# schematic.net
KiCad netlist of a schematic drawn in EasyEDA
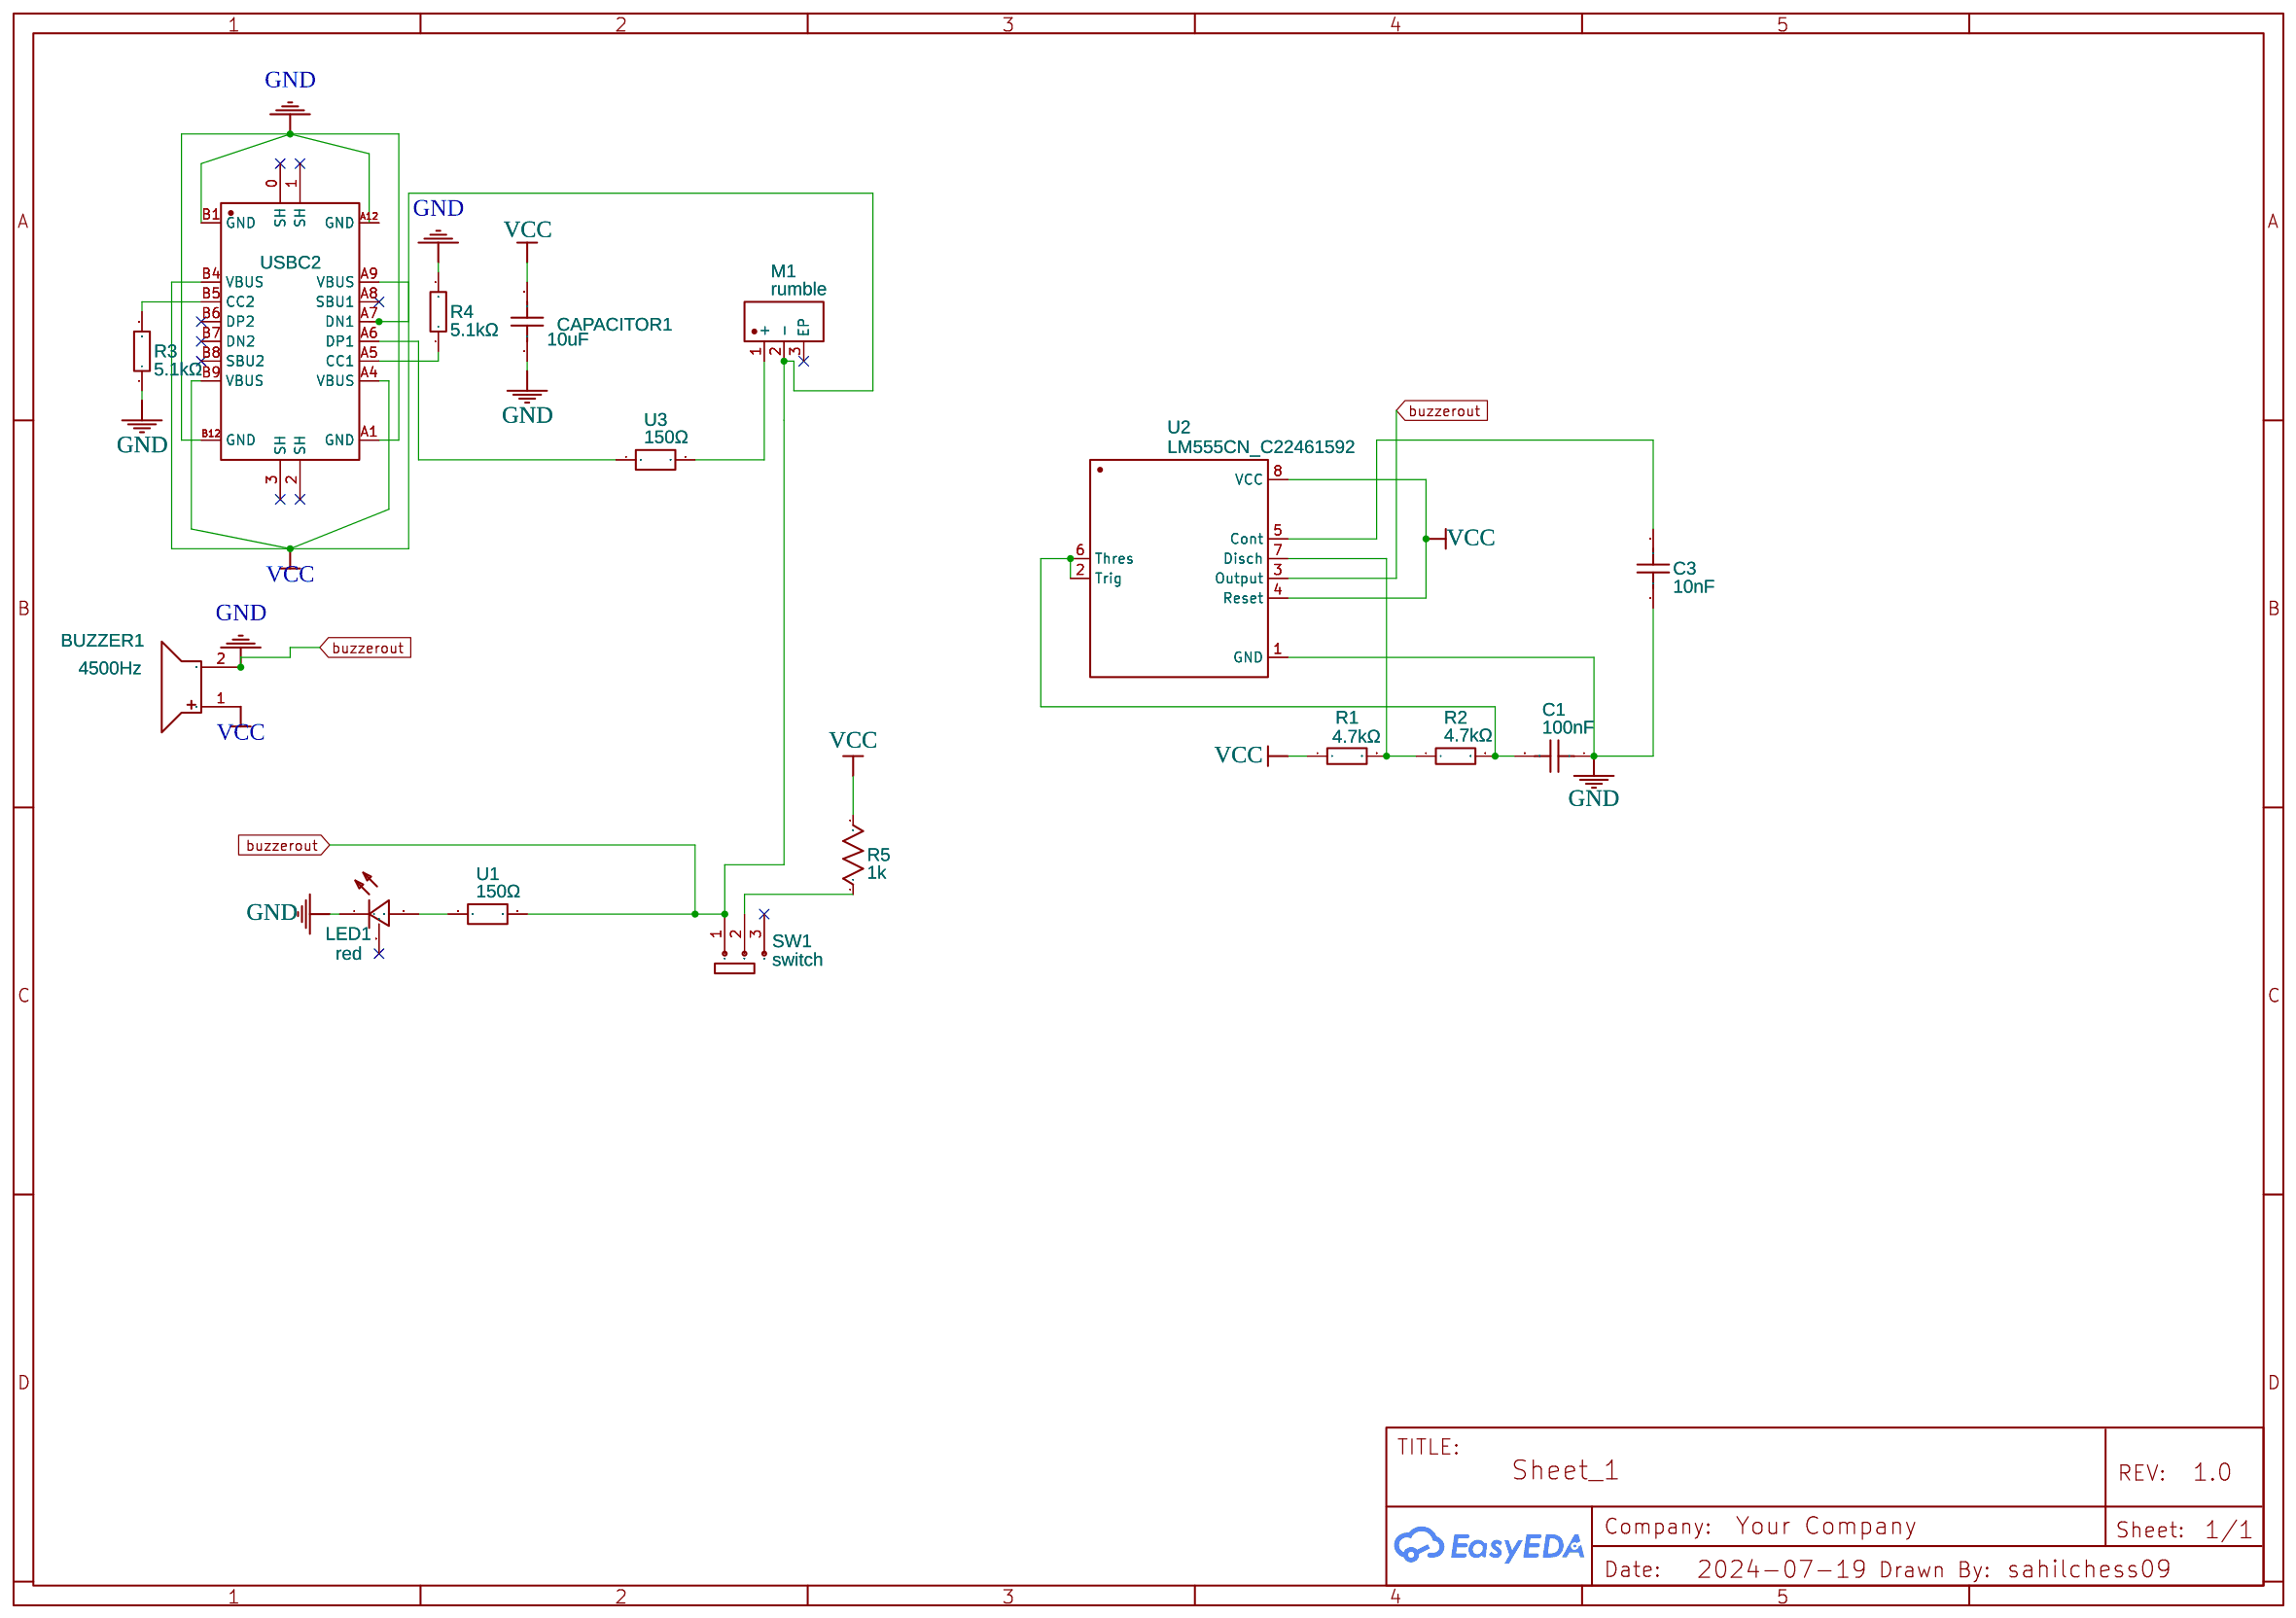
[diagram p0: schematic sheet]

(export (version "E")
  (design (tool "Eeschema 10.0.6"))
  (components
    (comp (ref "BUZZER1")
      (value "4500Hz")
      (fields (field (name "Manufacturer Part") "HND-1407B") (field (name "Manufacturer") "华能"))
      (libsource (lib "") (part "HND-1407B"))
    )
    (comp (ref "C1")
      (value "100nF")
      (fields
        (field (name "Manufacturer Part") "MPX104K31D2KN15800")
        (field (name "Manufacturer") "KNSCHA(科尼盛)")
      )
      (libsource (lib "") (part "MPX104K31D2KN15800"))
    )
    (comp (ref "C3")
      (value "10nF")
      (fields
        (field (name "Manufacturer Part") "B1030630-D-10-3R")
        (field (name "Manufacturer") "GDHY(广东华裕)")
      )
      (libsource (lib "") (part "B1030630-D-10-3R"))
    )
    (comp (ref "CAPACITOR1")
      (value "10uF")
      (fields
        (field (name "Manufacturer Part") "CL10A106KP8NNNC")
        (field (name "Manufacturer") "SAMSUNG(三星)")
      )
      (libsource (lib "") (part "CL10A106KP8NNNC"))
    )
    (comp (ref "LED1")
      (value "red")
      (fields
        (field (name "Manufacturer Part") "TJ-S3210SW5TGLC2R-A5")
        (field (name "Manufacturer") "TOGIALED(统佳)")
      )
      (libsource (lib "") (part "TJ-S3210SW5TGLC2R-A5"))
    )
    (comp (ref "M1")
      (value "rumble")
      (fields (field (name "Manufacturer Part") "Z3OC1T8219731") (field (name "Manufacturer") "KOTL(金龙机电)"))
      (libsource (lib "") (part "Z3OC1T8219731"))
    )
    (comp (ref "R1")
      (value "4.7kΩ")
      (fields
        (field (name "Manufacturer Part") "MF1/4W-4.7KΩ±1% T")
        (field (name "Manufacturer") "CCO(千志电子)")
      )
      (libsource (lib "") (part "MF1/4W-4.7KΩ±1% T52"))
    )
    (comp (ref "R2")
      (value "4.7kΩ")
      (fields
        (field (name "Manufacturer Part") "MF1/4W-4.7KΩ±1% T")
        (field (name "Manufacturer") "CCO(千志电子)")
      )
      (libsource (lib "") (part "MF1/4W-4.7KΩ±1% T52"))
    )
    (comp (ref "R3")
      (value "5.1kΩ")
      (fields (field (name "Manufacturer Part") "RMC08055.1K1%N") (field (name "Manufacturer") "Tyohm(幸亚电阻)"))
      (libsource (lib "") (part "RMC08055.1K1%N"))
    )
    (comp (ref "R4")
      (value "5.1kΩ")
      (fields (field (name "Manufacturer Part") "RMC08055.1K1%N") (field (name "Manufacturer") "Tyohm(幸亚电阻)"))
      (libsource (lib "") (part "RMC08055.1K1%N"))
    )
    (comp (ref "R5") (value "1k") (libsource (lib "") (part "R_0603_US")))
    (comp (ref "SW1")
      (value "switch")
      (fields (field (name "Manufacturer Part") "K3-1235S-L1") (field (name "Manufacturer") "韩国韩荣"))
      (libsource (lib "") (part "K3-1235S-L1"))
    )
    (comp (ref "U1")
      (value "150Ω")
      (fields
        (field (name "Manufacturer Part") "TNPW0402150RBYEP")
        (field (name "Manufacturer") "VISHAY(威世)")
      )
      (libsource (lib "") (part "TNPW0402150RBYEP"))
    )
    (comp (ref "U2")
      (value "LM555CN_C22461592")
      (fields (field (name "Manufacturer Part") "LM555CN") (field (name "Manufacturer") "HGSEMI(华冠)"))
      (libsource (lib "") (part "LM555CN_C22461592"))
    )
    (comp (ref "U3")
      (value "150Ω")
      (fields
        (field (name "Manufacturer Part") "TNPW0402150RBYEP")
        (field (name "Manufacturer") "VISHAY(威世)")
      )
      (libsource (lib "") (part "TNPW0402150RBYEP"))
    )
    (comp (ref "USBC2")
      (value "TYPE-C-31-M-12")
      (fields (field (name "Manufacturer") "韩国韩荣"))
      (libsource (lib "") (part "TYPE-C-31-M-12"))
    )
  )
  (nets
    (net (code "1") (name "Net-(LED1-Pad2)") (class "Default")
      (node (ref "LED1") (pin "2") (pinfunction "2_2") (pintype "unspecified"))
      (node (ref "U1") (pin "1") (pinfunction "1_1") (pintype "unspecified"))
    )
    (net (code "2") (name "Net-(M1-+)") (class "Default")
      (node (ref "M1") (pin "1") (pinfunction "+_1") (pintype "unspecified"))
      (node (ref "U3") (pin "2") (pinfunction "2_2") (pintype "unspecified"))
    )
    (net (code "3") (name "Net-(R5-Pad1)") (class "Default")
      (node (ref "R5") (pin "1") (pinfunction "1_1") (pintype "unspecified"))
      (node (ref "SW1") (pin "2") (pinfunction "2_2") (pintype "unspecified"))
    )
    (net (code "4") (name "Net-(U2-Cont)") (class "Default")
      (node (ref "C3") (pin "2") (pinfunction "2_2") (pintype "unspecified"))
      (node (ref "U2") (pin "5") (pinfunction "Cont_5") (pintype "unspecified"))
    )
    (net (code "5") (name "Net-(U2-Disch)") (class "Default")
      (node (ref "R1") (pin "2") (pinfunction "2_2") (pintype "unspecified"))
      (node (ref "R2") (pin "1") (pinfunction "1_1") (pintype "unspecified"))
      (node (ref "U2") (pin "7") (pinfunction "Disch_7") (pintype "unspecified"))
    )
    (net (code "6") (name "Net-(U2-Thres)") (class "Default")
      (node (ref "C1") (pin "2") (pinfunction "2_2") (pintype "unspecified"))
      (node (ref "R2") (pin "2") (pinfunction "2_2") (pintype "unspecified"))
      (node (ref "U2") (pin "2") (pinfunction "Trig_2") (pintype "unspecified"))
      (node (ref "U2") (pin "6") (pinfunction "Thres_6") (pintype "unspecified"))
    )
    (net (code "7") (name "Net-(USBC2-CC1)") (class "Default")
      (node (ref "R4") (pin "1") (pinfunction "1_1") (pintype "unspecified"))
      (node (ref "USBC2") (pin "A5") (pinfunction "CC1_A5") (pintype "unspecified"))
    )
    (net (code "8") (name "Net-(USBC2-CC2)") (class "Default")
      (node (ref "R3") (pin "2") (pinfunction "2_2") (pintype "unspecified"))
      (node (ref "USBC2") (pin "B5") (pinfunction "CC2_B5") (pintype "unspecified"))
    )
    (net (code "9") (name "Net-(USBC2-DP1)") (class "Default")
      (node (ref "U3") (pin "1") (pinfunction "1_1") (pintype "unspecified"))
      (node (ref "USBC2") (pin "A6") (pinfunction "DP1_A6") (pintype "unspecified"))
    )
    (net (code "10") (name "VCC") (class "Default")
      (node (ref "BUZZER1") (pin "1") (pinfunction "1_1") (pintype "unspecified"))
      (node (ref "CAPACITOR1") (pin "2") (pinfunction "2_2") (pintype "unspecified"))
      (node (ref "R1") (pin "1") (pinfunction "1_1") (pintype "unspecified"))
      (node (ref "R5") (pin "2") (pinfunction "2_2") (pintype "unspecified"))
      (node (ref "U2") (pin "4") (pinfunction "Reset_4") (pintype "unspecified"))
      (node (ref "U2") (pin "8") (pinfunction "VCC_8") (pintype "unspecified"))
      (node (ref "USBC2") (pin "A4") (pinfunction "VBUS_A4") (pintype "unspecified"))
      (node (ref "USBC2") (pin "A9") (pinfunction "VBUS_A9") (pintype "unspecified"))
      (node (ref "USBC2") (pin "B4") (pinfunction "VBUS_B4") (pintype "unspecified"))
      (node (ref "USBC2") (pin "B9") (pinfunction "VBUS_B9") (pintype "unspecified"))
    )
    (net (code "11") (name "buzzerout") (class "Default")
      (node (ref "BUZZER1") (pin "2") (pinfunction "2_2") (pintype "unspecified"))
      (node (ref "C1") (pin "1") (pinfunction "1_1") (pintype "unspecified"))
      (node (ref "C3") (pin "1") (pinfunction "1_1") (pintype "unspecified"))
      (node (ref "CAPACITOR1") (pin "1") (pinfunction "1_1") (pintype "unspecified"))
      (node (ref "LED1") (pin "1") (pinfunction "1_1") (pintype "unspecified"))
      (node (ref "M1") (pin "2") (pinfunction "-_2") (pintype "unspecified"))
      (node (ref "R3") (pin "1") (pinfunction "1_1") (pintype "unspecified"))
      (node (ref "R4") (pin "2") (pinfunction "2_2") (pintype "unspecified"))
      (node (ref "SW1") (pin "1") (pinfunction "1_1") (pintype "unspecified"))
      (node (ref "U1") (pin "2") (pinfunction "2_2") (pintype "unspecified"))
      (node (ref "U2") (pin "1") (pinfunction "GND_1") (pintype "unspecified"))
      (node (ref "U2") (pin "3") (pinfunction "Output_3") (pintype "unspecified"))
      (node (ref "USBC2") (pin "A1") (pinfunction "GND_A1") (pintype "unspecified"))
      (node (ref "USBC2") (pin "A12") (pinfunction "GND_A12") (pintype "unspecified"))
      (node (ref "USBC2") (pin "A7") (pinfunction "DN1_A7") (pintype "unspecified"))
      (node (ref "USBC2") (pin "B1") (pinfunction "GND_B1") (pintype "unspecified"))
      (node (ref "USBC2") (pin "B12") (pinfunction "GND_B12") (pintype "unspecified"))
    )
    (net (code "12") (name "unconnected-(LED1-Pad3)") (class "Default")
      (node (ref "LED1") (pin "3") (pinfunction "3_3") (pintype "unspecified+no_connect"))
    )
    (net (code "13") (name "unconnected-(M1-EP-Pad3)") (class "Default")
      (node (ref "M1") (pin "3") (pinfunction "EP_3") (pintype "unspecified+no_connect"))
    )
    (net (code "14") (name "unconnected-(SW1-Pad3)") (class "Default")
      (node (ref "SW1") (pin "3") (pinfunction "3_3") (pintype "unspecified+no_connect"))
    )
    (net (code "15") (name "unconnected-(USBC2-DN2-PadB7)") (class "Default")
      (node (ref "USBC2") (pin "B7") (pinfunction "DN2_B7") (pintype "unspecified+no_connect"))
    )
    (net (code "16") (name "unconnected-(USBC2-DP2-PadB6)") (class "Default")
      (node (ref "USBC2") (pin "B6") (pinfunction "DP2_B6") (pintype "unspecified+no_connect"))
    )
    (net (code "17") (name "unconnected-(USBC2-SBU1-PadA8)") (class "Default")
      (node (ref "USBC2") (pin "A8") (pinfunction "SBU1_A8") (pintype "unspecified+no_connect"))
    )
    (net (code "18") (name "unconnected-(USBC2-SBU2-PadB8)") (class "Default")
      (node (ref "USBC2") (pin "B8") (pinfunction "SBU2_B8") (pintype "unspecified+no_connect"))
    )
    (net (code "19") (name "unconnected-(USBC2-SH-Pad0)") (class "Default")
      (node (ref "USBC2") (pin "0") (pinfunction "SH_0") (pintype "unspecified+no_connect"))
    )
    (net (code "20") (name "unconnected-(USBC2-SH-Pad1)") (class "Default")
      (node (ref "USBC2") (pin "1") (pinfunction "SH_1") (pintype "unspecified+no_connect"))
    )
    (net (code "21") (name "unconnected-(USBC2-SH-Pad2)") (class "Default")
      (node (ref "USBC2") (pin "2") (pinfunction "SH_2") (pintype "unspecified+no_connect"))
    )
    (net (code "22") (name "unconnected-(USBC2-SH-Pad3)") (class "Default")
      (node (ref "USBC2") (pin "3") (pinfunction "SH_3") (pintype "unspecified+no_connect"))
    )
  )
)
